# Power.net
KiCad netlist of a schematic drawn in Altium Designer
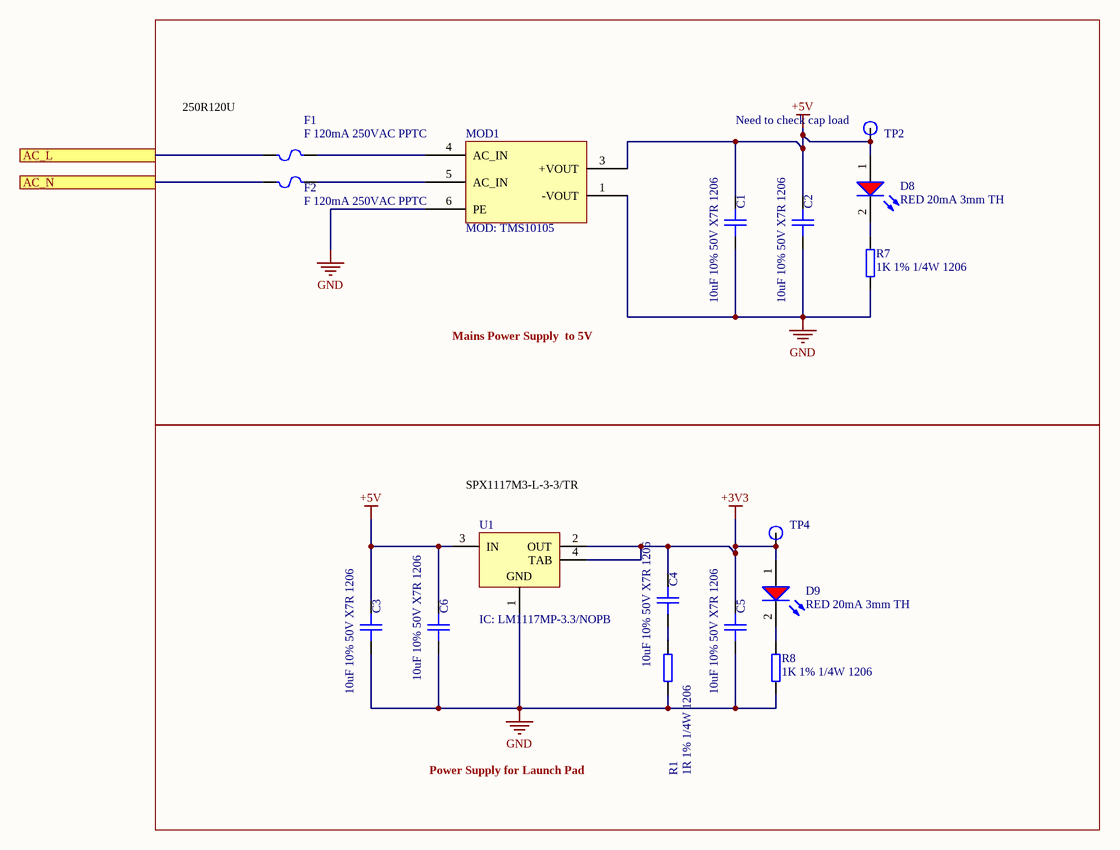
[diagram p0: Power.SchDoc]

(export (version "E")
  (design (tool "Eeschema 10.0.6"))
  (components
    (comp (ref "C1")
      (value "10uF 10% 50V X7R 1206")
      (footprint "CAPC3216X18N")
      (fields
        (field (name "MANUFACTURER PART NUMBER") "C3216X7R1H106K160AC")
        (field (name "MANUFACTURER") "TDK")
      )
      (libsource (lib "EMEA- E-Tech Racing- I'Escola d'Enginyeria de Barcelona Est") (part "68pF 10 630V C0G 0805"))
    )
    (comp (ref "C2")
      (value "10uF 10% 50V X7R 1206")
      (footprint "CAPC3216X18N")
      (fields
        (field (name "MANUFACTURER PART NUMBER") "C3216X7R1H106K160AC")
        (field (name "MANUFACTURER") "TDK")
      )
      (libsource (lib "EMEA- E-Tech Racing- I'Escola d'Enginyeria de Barcelona Est") (part "68pF 10 630V C0G 0805"))
    )
    (comp (ref "C3")
      (value "10uF 10% 50V X7R 1206")
      (footprint "CAPC3216X18N")
      (fields
        (field (name "MANUFACTURER PART NUMBER") "C3216X7R1H106K160AC")
        (field (name "MANUFACTURER") "TDK")
      )
      (libsource (lib "EMEA- E-Tech Racing- I'Escola d'Enginyeria de Barcelona Est") (part "68pF 10 630V C0G 0805"))
    )
    (comp (ref "C4")
      (value "10uF 10% 50V X7R 1206")
      (footprint "CAPC3216X18N")
      (fields
        (field (name "MANUFACTURER PART NUMBER") "C3216X7R1H106K160AC")
        (field (name "MANUFACTURER") "TDK")
      )
      (libsource (lib "EMEA- E-Tech Racing- I'Escola d'Enginyeria de Barcelona Est") (part "68pF 10 630V C0G 0805"))
    )
    (comp (ref "C5")
      (value "10uF 10% 50V X7R 1206")
      (footprint "CAPC3216X18N")
      (fields
        (field (name "MANUFACTURER PART NUMBER") "C3216X7R1H106K160AC")
        (field (name "MANUFACTURER") "TDK")
      )
      (libsource (lib "EMEA- E-Tech Racing- I'Escola d'Enginyeria de Barcelona Est") (part "68pF 10 630V C0G 0805"))
    )
    (comp (ref "C6")
      (value "10uF 10% 50V X7R 1206")
      (footprint "CAPC3216X18N")
      (fields
        (field (name "MANUFACTURER PART NUMBER") "C3216X7R1H106K160AC")
        (field (name "MANUFACTURER") "TDK")
      )
      (libsource (lib "EMEA- E-Tech Racing- I'Escola d'Enginyeria de Barcelona Est") (part "68pF 10 630V C0G 0805"))
    )
    (comp (ref "D8")
      (value "RED 20mA 3mm TH")
      (footprint "WL-TMRC_D3.95H5.3")
      (description "LED RED DIFFUSED 3MM ROUND T/H")
      (fields
        (field (name "MANUFACTURER") "Wurth Elektronik")
        (field (name "MANUFACTURER PART NUMBER") "151031SS06000")
      )
      (libsource (lib "EMEA- E-Tech Racing- I'Escola d'Enginyeria de Barcelona Est") (part "LED_Red_1A-2K"))
    )
    (comp (ref "D9")
      (value "RED 20mA 3mm TH")
      (footprint "WL-TMRC_D3.95H5.3")
      (description "LED RED DIFFUSED 3MM ROUND T/H")
      (fields
        (field (name "MANUFACTURER") "Wurth Elektronik")
        (field (name "MANUFACTURER PART NUMBER") "151031SS06000")
      )
      (libsource (lib "EMEA- E-Tech Racing- I'Escola d'Enginyeria de Barcelona Est") (part "LED_Red_1A-2K"))
    )
    (comp (ref "F1")
      (value "F 120mA 250VAC PPTC")
      (footprint "New footprint 1")
      (description "Polymeric PTC Resettable Fuse 60V (250V Int) 120 mA Ih Through Hole Radial, Disc")
      (fields (field (name "MANUFACTURER PART NUMBER") "250R120U") (field (name "MANUFACTURER") "Littelfuse"))
      (libsource (lib "EMEA- E-Tech Racing- I'Escola d'Enginyeria de Barcelona Est") (part "F 120mA 250VAC PPTC-Symbol-1"))
    )
    (comp (ref "F2")
      (value "F 120mA 250VAC PPTC")
      (footprint "New footprint 1")
      (description "Polymeric PTC Resettable Fuse 60V (250V Int) 120 mA Ih Through Hole Radial, Disc")
      (fields (field (name "MANUFACTURER PART NUMBER") "250R120U") (field (name "MANUFACTURER") "Littelfuse"))
      (libsource (lib "EMEA- E-Tech Racing- I'Escola d'Enginyeria de Barcelona Est") (part "F 120mA 250VAC PPTC-Symbol-1"))
    )
    (comp (ref "MOD1")
      (value "MOD: TMS10105")
      (footprint "MOD: TMS10105-Footprint-1")
      (description "AC-DC Regulated Power Supply Module, 1 Output, 10W, 5V Output Hybrid")
      (fields
        (field (name "MANUFACTURER PART NUMBER") "TMS10105")
        (field (name "MANUFACTURER") "Traco Power")
      )
      (libsource (lib "EMEA- E-Tech Racing- I'Escola d'Enginyeria de Barcelona Est") (part "TMS10105-Symbol-1"))
    )
    (comp (ref "R1")
      (value "1R 1% 1/4W 1206")
      (footprint "RESC3116X06N")
      (description "Res Thick Film 1206 1 Ohm 1% 0.25W(1/4W) ±100ppm/C Pad SMD T/R Automotive AEC-Q200")
      (fields (field (name "MANUFACTURER") "Stackpole Electronics") (field (name "TOLERANCE") "1%"))
      (libsource (lib "EMEA- E-Tech Racing- I'Escola d'Enginyeria de Barcelona Est") (part "100R 1 1/8W 0805"))
    )
    (comp (ref "R7")
      (value "1K 1% 1/4W 1206")
      (footprint "RESC3116X06N")
      (description "Res Thick Film 1206 1K Ohm 1% 0.25W(1/4W) ±100ppm/C Pad SMD T/R Automotive AEC-Q200")
      (fields
        (field (name "MANUFACTURER PART NUMBER") "RMCF1206FT1K00")
        (field (name "MANUFACTURER") "Stackpole Electronics")
      )
      (libsource (lib "EMEA- E-Tech Racing- I'Escola d'Enginyeria de Barcelona Est") (part "100R 1 1/8W 0805"))
    )
    (comp (ref "R8")
      (value "1K 1% 1/4W 1206")
      (footprint "RESC3116X06N")
      (description "Res Thick Film 1206 1K Ohm 1% 0.25W(1/4W) ±100ppm/C Pad SMD T/R Automotive AEC-Q200")
      (fields
        (field (name "MANUFACTURER PART NUMBER") "RMCF1206FT1K00")
        (field (name "MANUFACTURER") "Stackpole Electronics")
      )
      (libsource (lib "EMEA- E-Tech Racing- I'Escola d'Enginyeria de Barcelona Est") (part "100R 1 1/8W 0805"))
    )
    (comp (ref "TP2")
      (value "TestPoint")
      (footprint "Test Point-Footprint-1")
      (libsource (lib "EMEA- E-Tech Racing- I'Escola d'Enginyeria de Barcelona Est") (part "New symbol 1"))
    )
    (comp (ref "TP4")
      (value "TestPoint")
      (footprint "Test Point-Footprint-1")
      (libsource (lib "EMEA- E-Tech Racing- I'Escola d'Enginyeria de Barcelona Est") (part "New symbol 1"))
    )
    (comp (ref "U1")
      (value "IC: LM1117MP-3.3/NOPB")
      (footprint "DCY0004A_M")
      (description "Texas Instruments LM1117MP-3.3/NOPB. Ldo Voltage Regulator, 3.3V, 0.8A, SOT-223-4, Full Reel")
      (fields
        (field (name "MANUFACTURER") "SOT-223")
        (field (name "MANUFACTURER PART NUMBER") "LM1117MP-3.3/NOPB")
      )
      (libsource (lib "EMEA- E-Tech Racing- I'Escola d'Enginyeria de Barcelona Est") (part "PM-REG-LM1086-SOT4"))
    )
  )
  (nets
    (net (code "1") (name "+3V3") (class "Default")
      (node (ref "C4") (pin "2") (pinfunction "2_2") (pintype "passive"))
      (node (ref "C5") (pin "2") (pinfunction "2_2") (pintype "passive"))
      (node (ref "D9") (pin "1") (pinfunction "A_1") (pintype "passive"))
      (node (ref "TP4") (pin "1") (pinfunction "1_1") (pintype "passive"))
      (node (ref "U1") (pin "2") (pinfunction "OUT_2") (pintype "power_in"))
      (node (ref "U1") (pin "4") (pinfunction "TAB_4") (pintype "power_in"))
    )
    (net (code "2") (name "+5V") (class "Default")
      (node (ref "C1") (pin "2") (pinfunction "2_2") (pintype "passive"))
      (node (ref "C2") (pin "2") (pinfunction "2_2") (pintype "passive"))
      (node (ref "C3") (pin "2") (pinfunction "2_2") (pintype "passive"))
      (node (ref "C6") (pin "2") (pinfunction "2_2") (pintype "passive"))
      (node (ref "D8") (pin "1") (pinfunction "A_1") (pintype "passive"))
      (node (ref "MOD1") (pin "3") (pinfunction "+VOUT_3") (pintype "passive"))
      (node (ref "TP2") (pin "1") (pinfunction "1_1") (pintype "passive"))
      (node (ref "U1") (pin "3") (pinfunction "IN_3") (pintype "power_in"))
    )
    (net (code "3") (name "/AC_L") (class "Default")
      (node (ref "F1") (pin "1") (pinfunction "1_1") (pintype "passive"))
    )
    (net (code "4") (name "/AC_N") (class "Default")
      (node (ref "F2") (pin "1") (pinfunction "1_1") (pintype "passive"))
    )
    (net (code "5") (name "GND") (class "Default")
      (node (ref "C1") (pin "1") (pinfunction "1_1") (pintype "passive"))
      (node (ref "C2") (pin "1") (pinfunction "1_1") (pintype "passive"))
      (node (ref "C3") (pin "1") (pinfunction "1_1") (pintype "passive"))
      (node (ref "C5") (pin "1") (pinfunction "1_1") (pintype "passive"))
      (node (ref "C6") (pin "1") (pinfunction "1_1") (pintype "passive"))
      (node (ref "MOD1") (pin "1") (pinfunction "-VOUT_1") (pintype "passive"))
      (node (ref "MOD1") (pin "6") (pinfunction "PE_6") (pintype "passive"))
      (node (ref "R1") (pin "1") (pinfunction "1_1") (pintype "passive"))
      (node (ref "R7") (pin "1") (pinfunction "1_1") (pintype "passive"))
      (node (ref "R8") (pin "1") (pinfunction "1_1") (pintype "passive"))
      (node (ref "U1") (pin "1") (pinfunction "GND_1") (pintype "power_in"))
    )
    (net (code "6") (name "Net-(C4-Pad1)") (class "Default")
      (node (ref "C4") (pin "1") (pinfunction "1_1") (pintype "passive"))
      (node (ref "R1") (pin "2") (pinfunction "2_2") (pintype "passive"))
    )
    (net (code "7") (name "Net-(D8-K)") (class "Default")
      (node (ref "D8") (pin "2") (pinfunction "K_2") (pintype "passive"))
      (node (ref "R7") (pin "2") (pinfunction "2_2") (pintype "passive"))
    )
    (net (code "8") (name "Net-(D9-K)") (class "Default")
      (node (ref "D9") (pin "2") (pinfunction "K_2") (pintype "passive"))
      (node (ref "R8") (pin "2") (pinfunction "2_2") (pintype "passive"))
    )
    (net (code "9") (name "Net-(F1-Pad2)") (class "Default")
      (node (ref "F1") (pin "2") (pinfunction "2_2") (pintype "passive"))
      (node (ref "MOD1") (pin "4") (pinfunction "AC_IN_4") (pintype "passive"))
    )
    (net (code "10") (name "Net-(F2-Pad2)") (class "Default")
      (node (ref "F2") (pin "2") (pinfunction "2_2") (pintype "passive"))
      (node (ref "MOD1") (pin "5") (pinfunction "AC_IN_5") (pintype "passive"))
    )
  )
)
